# esp8266-relay.net
KiCad netlist of a schematic drawn in EAGLE
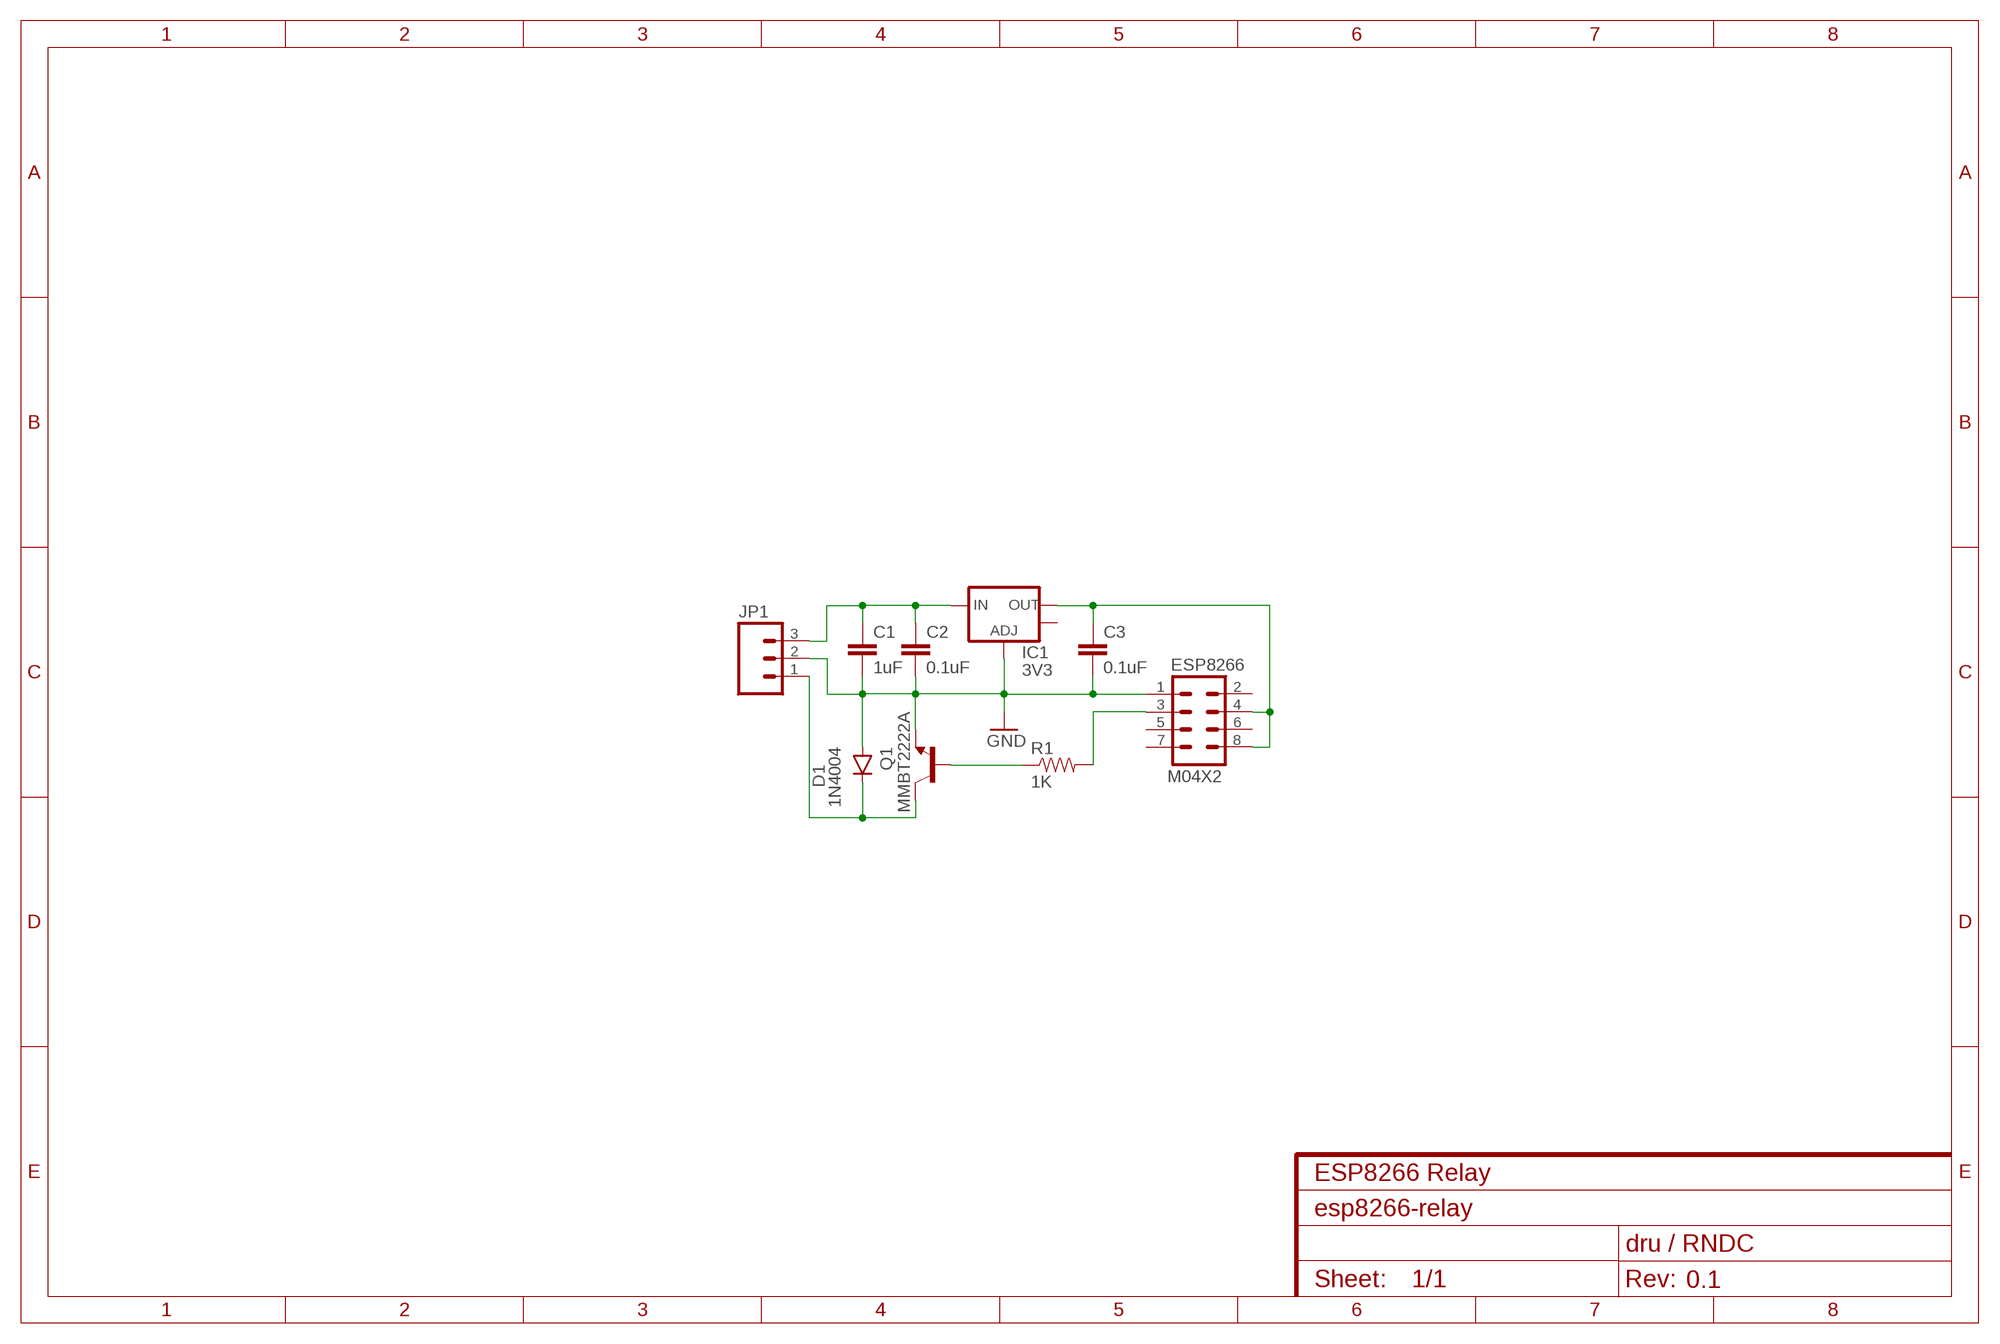
[diagram p0: schematic, sheet 1]

(export (version "E")
  (design (tool "Eeschema 10.0.6"))
  (components
    (comp (ref "C1")
      (value "1uF")
      (footprint "eagle-import:0603-CAP")
      (libsource (lib "eagle-import") (part "CAP0603-CAP"))
    )
    (comp (ref "C2")
      (value "0.1uF")
      (footprint "eagle-import:0805")
      (libsource (lib "eagle-import") (part "CAP0805"))
    )
    (comp (ref "C3")
      (value "0.1uF")
      (footprint "eagle-import:0805")
      (libsource (lib "eagle-import") (part "CAP0805"))
    )
    (comp (ref "D1")
      (value "1N4004")
      (footprint "eagle-import:SMA-DIODE_ALT")
      (libsource (lib "eagle-import") (part "DIODESMA-ALT"))
    )
    (comp (ref "ESP8266")
      (value "M04X2")
      (footprint "eagle-import:2X4")
      (libsource (lib "eagle-import") (part "M04X2"))
    )
    (comp (ref "IC1")
      (value "3V3")
      (footprint "eagle-import:SOT223")
      (libsource (lib "eagle-import") (part "V_REG_LM1117SOT223"))
    )
    (comp (ref "JP1")
      (value "M03PTH")
      (footprint "eagle-import:1X03")
      (libsource (lib "eagle-import") (part "M03PTH"))
    )
    (comp (ref "Q1")
      (value "MMBT2222A")
      (footprint "eagle-import:SOT23-3")
      (libsource (lib "eagle-import") (part "TRANSISTOR_NPNMMBT2222A"))
    )
    (comp (ref "R1")
      (value "1K")
      (footprint "eagle-import:0603-RES")
      (libsource (lib "eagle-import") (part "RESISTOR0603-RES"))
    )
  )
  (nets
    (net (code "1") (name "GND") (class "Default")
      (node (ref "C1") (pin "2") (pinfunction "2_2") (pintype "passive"))
      (node (ref "C2") (pin "2") (pinfunction "2_2") (pintype "passive"))
      (node (ref "C3") (pin "2") (pinfunction "2_2") (pintype "passive"))
      (node (ref "D1") (pin "A") (pinfunction "A_A") (pintype "passive"))
      (node (ref "ESP8266") (pin "1") (pinfunction "1_1") (pintype "passive"))
      (node (ref "IC1") (pin "1") (pinfunction "ADJ_1") (pintype "input"))
      (node (ref "JP1") (pin "2") (pinfunction "2_2") (pintype "passive"))
      (node (ref "Q1") (pin "2") (pinfunction "E_2") (pintype "passive"))
    )
    (net (code "2") (name "Net-(C3-Pad1)") (class "Default")
      (node (ref "C3") (pin "1") (pinfunction "1_1") (pintype "passive"))
      (node (ref "ESP8266") (pin "4") (pinfunction "4_4") (pintype "passive"))
      (node (ref "ESP8266") (pin "8") (pinfunction "8_8") (pintype "passive"))
      (node (ref "IC1") (pin "2") (pinfunction "OUT_2") (pintype "output"))
    )
    (net (code "3") (name "Net-(ESP8266-Pad3)") (class "Default")
      (node (ref "ESP8266") (pin "3") (pinfunction "3_3") (pintype "passive"))
      (node (ref "R1") (pin "2") (pinfunction "2_2") (pintype "passive"))
    )
    (net (code "4") (name "Net-(IC1-IN)") (class "Default")
      (node (ref "C1") (pin "1") (pinfunction "1_1") (pintype "passive"))
      (node (ref "C2") (pin "1") (pinfunction "1_1") (pintype "passive"))
      (node (ref "IC1") (pin "3") (pinfunction "IN_3") (pintype "input"))
      (node (ref "JP1") (pin "3") (pinfunction "3_3") (pintype "passive"))
    )
    (net (code "5") (name "Net-(Q1-B)") (class "Default")
      (node (ref "Q1") (pin "1") (pinfunction "B_1") (pintype "passive"))
      (node (ref "R1") (pin "1") (pinfunction "1_1") (pintype "passive"))
    )
    (net (code "6") (name "Net-(Q1-C)") (class "Default")
      (node (ref "D1") (pin "C") (pinfunction "C_C") (pintype "passive"))
      (node (ref "JP1") (pin "1") (pinfunction "1_1") (pintype "passive"))
      (node (ref "Q1") (pin "3") (pinfunction "C_3") (pintype "passive"))
    )
    (net (code "7") (name "unconnected-(ESP8266-Pad2)") (class "Default")
      (node (ref "ESP8266") (pin "2") (pinfunction "2_2") (pintype "passive"))
    )
    (net (code "8") (name "unconnected-(ESP8266-Pad5)") (class "Default")
      (node (ref "ESP8266") (pin "5") (pinfunction "5_5") (pintype "passive"))
    )
    (net (code "9") (name "unconnected-(ESP8266-Pad6)") (class "Default")
      (node (ref "ESP8266") (pin "6") (pinfunction "6_6") (pintype "passive"))
    )
    (net (code "10") (name "unconnected-(ESP8266-Pad7)") (class "Default")
      (node (ref "ESP8266") (pin "7") (pinfunction "7_7") (pintype "passive"))
    )
    (net (code "11") (name "unconnected-(IC1-OUT-Pad4)") (class "Default")
      (node (ref "IC1") (pin "4") (pinfunction "OUT_4") (pintype "output"))
    )
  )
)
